# MBusAdapter.net
KiCad netlist of a schematic drawn in EAGLE
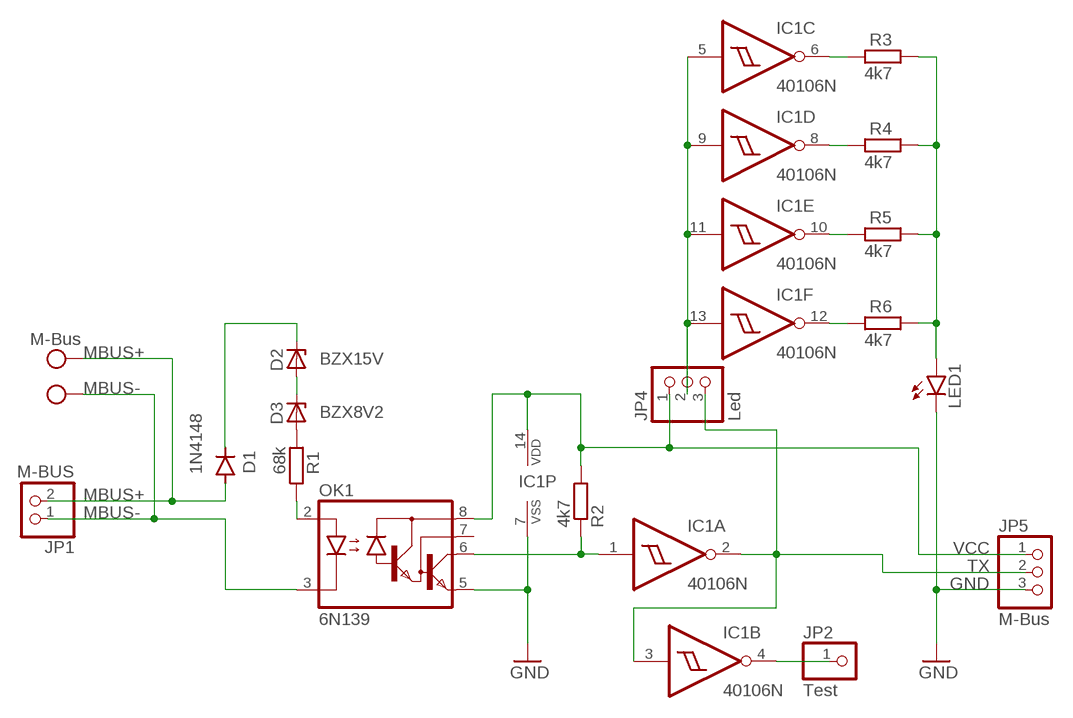
[diagram p0: schematic, sheet 1]

(export (version "E")
  (design (tool "Eeschema 10.0.6"))
  (components
    (comp (ref "D1")
      (value "1N4148")
      (footprint "eagle-import:DO35-10")
      (libsource (lib "eagle-import") (part "1N4148DO35-10"))
    )
    (comp (ref "D2")
      (value "BZX15V")
      (footprint "eagle-import:DO34Z7")
      (libsource (lib "eagle-import") (part "ZENER-DIODEDO34-7"))
    )
    (comp (ref "D3")
      (value "BZX8V2")
      (footprint "eagle-import:DO34Z7")
      (libsource (lib "eagle-import") (part "ZENER-DIODEDO34-7"))
    )
    (comp (ref "IC1")
      (value "40106N")
      (footprint "eagle-import:DIL14")
      (libsource (lib "eagle-import") (part "40106N"))
    )
    (comp (ref "JP1")
      (value "M-BUS")
      (footprint "eagle-import:1X02")
      (libsource (lib "eagle-import") (part "PINHD-1X2"))
    )
    (comp (ref "JP2")
      (value "Test")
      (footprint "eagle-import:1X01")
      (libsource (lib "eagle-import") (part "PINHD-1X1"))
    )
    (comp (ref "JP4")
      (value "Led")
      (footprint "eagle-import:1X03")
      (libsource (lib "eagle-import") (part "PINHD-1X3"))
    )
    (comp (ref "JP5")
      (value "M-Bus")
      (footprint "eagle-import:1X03")
      (libsource (lib "eagle-import") (part "PINHD-1X3"))
    )
    (comp (ref "LED1")
      (value "TLLG4400")
      (footprint "eagle-import:LED3MM")
      (fields (field (name "MF") "VISHAY SEMICONDUCTOR"))
      (libsource (lib "eagle-import") (part "TLLG4400"))
    )
    (comp (ref "M-BUS")
      (value "M-Bus")
      (footprint "eagle-import:W237-102")
      (fields (field (name "MPN") "237-102"))
      (libsource (lib "eagle-import") (part "W237-102"))
    )
    (comp (ref "OK1")
      (value "6N139")
      (footprint "eagle-import:DIL08")
      (fields (field (name "MF") "VISHAY/TELEFUNKEN") (field (name "MPN") "6N138"))
      (libsource (lib "eagle-import") (part "6N138"))
    )
    (comp (ref "R1")
      (value "68k")
      (footprint "eagle-import:0207_10")
      (libsource (lib "eagle-import") (part "R-EU_0207/10"))
    )
    (comp (ref "R2")
      (value "4k7")
      (footprint "eagle-import:0207_10")
      (libsource (lib "eagle-import") (part "R-EU_0207/10"))
    )
    (comp (ref "R3")
      (value "4k7")
      (footprint "eagle-import:0207_10")
      (libsource (lib "eagle-import") (part "R-EU_0207/10"))
    )
    (comp (ref "R4")
      (value "4k7")
      (footprint "eagle-import:0207_10")
      (libsource (lib "eagle-import") (part "R-EU_0207/10"))
    )
    (comp (ref "R5")
      (value "4k7")
      (footprint "eagle-import:0207_10")
      (libsource (lib "eagle-import") (part "R-EU_0207/10"))
    )
    (comp (ref "R6")
      (value "4k7")
      (footprint "eagle-import:0207_10")
      (libsource (lib "eagle-import") (part "R-EU_0207/10"))
    )
  )
  (nets
    (net (code "1") (name "/MBUS+") (class "Default")
      (node (ref "D1") (pin "A") (pinfunction "A_A") (pintype "passive"))
      (node (ref "JP1") (pin "2") (pinfunction "2_2") (pintype "passive"))
      (node (ref "M-BUS") (pin "2") (pinfunction "KL_2") (pintype "passive"))
    )
    (net (code "2") (name "/MBUS-") (class "Default")
      (node (ref "JP1") (pin "1") (pinfunction "1_1") (pintype "passive"))
      (node (ref "M-BUS") (pin "1") (pinfunction "KL_1") (pintype "passive"))
      (node (ref "OK1") (pin "3") (pinfunction "C_3") (pintype "passive"))
    )
    (net (code "3") (name "/TX") (class "Default")
      (node (ref "IC1") (pin "2") (pinfunction "O_2") (pintype "output"))
      (node (ref "IC1") (pin "3") (pinfunction "I_3") (pintype "input"))
      (node (ref "JP4") (pin "3") (pinfunction "3_3") (pintype "passive"))
      (node (ref "JP5") (pin "2") (pinfunction "2_2") (pintype "passive"))
    )
    (net (code "4") (name "/VCC") (class "Default")
      (node (ref "IC1") (pin "14") (pinfunction "VDD_14") (pintype "power_in"))
      (node (ref "JP4") (pin "1") (pinfunction "1_1") (pintype "passive"))
      (node (ref "JP5") (pin "1") (pinfunction "1_1") (pintype "passive"))
      (node (ref "OK1") (pin "8") (pinfunction "VCC_8") (pintype "passive"))
      (node (ref "R2") (pin "2") (pinfunction "2_2") (pintype "passive"))
    )
    (net (code "5") (name "GND") (class "Default")
      (node (ref "IC1") (pin "7") (pinfunction "VSS_7") (pintype "power_in"))
      (node (ref "JP5") (pin "3") (pinfunction "3_3") (pintype "passive"))
      (node (ref "LED1") (pin "K") (pinfunction "C_K") (pintype "passive"))
      (node (ref "OK1") (pin "5") (pinfunction "GND_5") (pintype "passive"))
    )
    (net (code "6") (name "Net-(D1-PadC)") (class "Default")
      (node (ref "D1") (pin "C") (pinfunction "C_C") (pintype "passive"))
      (node (ref "D2") (pin "C") (pinfunction "C_C") (pintype "passive"))
    )
    (net (code "7") (name "Net-(D2-PadA)") (class "Default")
      (node (ref "D2") (pin "A") (pinfunction "A_A") (pintype "passive"))
      (node (ref "D3") (pin "C") (pinfunction "C_C") (pintype "passive"))
    )
    (net (code "8") (name "Net-(D3-PadA)") (class "Default")
      (node (ref "D3") (pin "A") (pinfunction "A_A") (pintype "passive"))
      (node (ref "R1") (pin "2") (pinfunction "2_2") (pintype "passive"))
    )
    (net (code "9") (name "Net-(IC1A-I)") (class "Default")
      (node (ref "IC1") (pin "1") (pinfunction "I_1") (pintype "input"))
      (node (ref "OK1") (pin "6") (pinfunction "VO_6") (pintype "passive"))
      (node (ref "R2") (pin "1") (pinfunction "1_1") (pintype "passive"))
    )
    (net (code "10") (name "Net-(IC1B-O)") (class "Default")
      (node (ref "IC1") (pin "4") (pinfunction "O_4") (pintype "output"))
      (node (ref "JP2") (pin "1") (pinfunction "1_1") (pintype "passive"))
    )
    (net (code "11") (name "Net-(IC1C-I)") (class "Default")
      (node (ref "IC1") (pin "11") (pinfunction "I_11") (pintype "input"))
      (node (ref "IC1") (pin "13") (pinfunction "I_13") (pintype "input"))
      (node (ref "IC1") (pin "5") (pinfunction "I_5") (pintype "input"))
      (node (ref "IC1") (pin "9") (pinfunction "I_9") (pintype "input"))
      (node (ref "JP4") (pin "2") (pinfunction "2_2") (pintype "passive"))
    )
    (net (code "12") (name "Net-(IC1C-O)") (class "Default")
      (node (ref "IC1") (pin "6") (pinfunction "O_6") (pintype "output"))
      (node (ref "R3") (pin "2") (pinfunction "2_2") (pintype "passive"))
    )
    (net (code "13") (name "Net-(IC1D-O)") (class "Default")
      (node (ref "IC1") (pin "8") (pinfunction "O_8") (pintype "output"))
      (node (ref "R4") (pin "2") (pinfunction "2_2") (pintype "passive"))
    )
    (net (code "14") (name "Net-(IC1E-O)") (class "Default")
      (node (ref "IC1") (pin "10") (pinfunction "O_10") (pintype "output"))
      (node (ref "R5") (pin "2") (pinfunction "2_2") (pintype "passive"))
    )
    (net (code "15") (name "Net-(IC1F-O)") (class "Default")
      (node (ref "IC1") (pin "12") (pinfunction "O_12") (pintype "output"))
      (node (ref "R6") (pin "2") (pinfunction "2_2") (pintype "passive"))
    )
    (net (code "16") (name "Net-(LED1-PadA)") (class "Default")
      (node (ref "LED1") (pin "A") (pinfunction "A_A") (pintype "passive"))
      (node (ref "R3") (pin "1") (pinfunction "1_1") (pintype "passive"))
      (node (ref "R4") (pin "1") (pinfunction "1_1") (pintype "passive"))
      (node (ref "R5") (pin "1") (pinfunction "1_1") (pintype "passive"))
      (node (ref "R6") (pin "1") (pinfunction "1_1") (pintype "passive"))
    )
    (net (code "17") (name "Net-(OK1-A)") (class "Default")
      (node (ref "OK1") (pin "2") (pinfunction "A_2") (pintype "passive"))
      (node (ref "R1") (pin "1") (pinfunction "1_1") (pintype "passive"))
    )
    (net (code "18") (name "unconnected-(OK1-VB-Pad7)") (class "Default")
      (node (ref "OK1") (pin "7") (pinfunction "VB_7") (pintype "passive"))
    )
  )
)
